# M202B.net
KiCad netlist of a schematic drawn in EAGLE
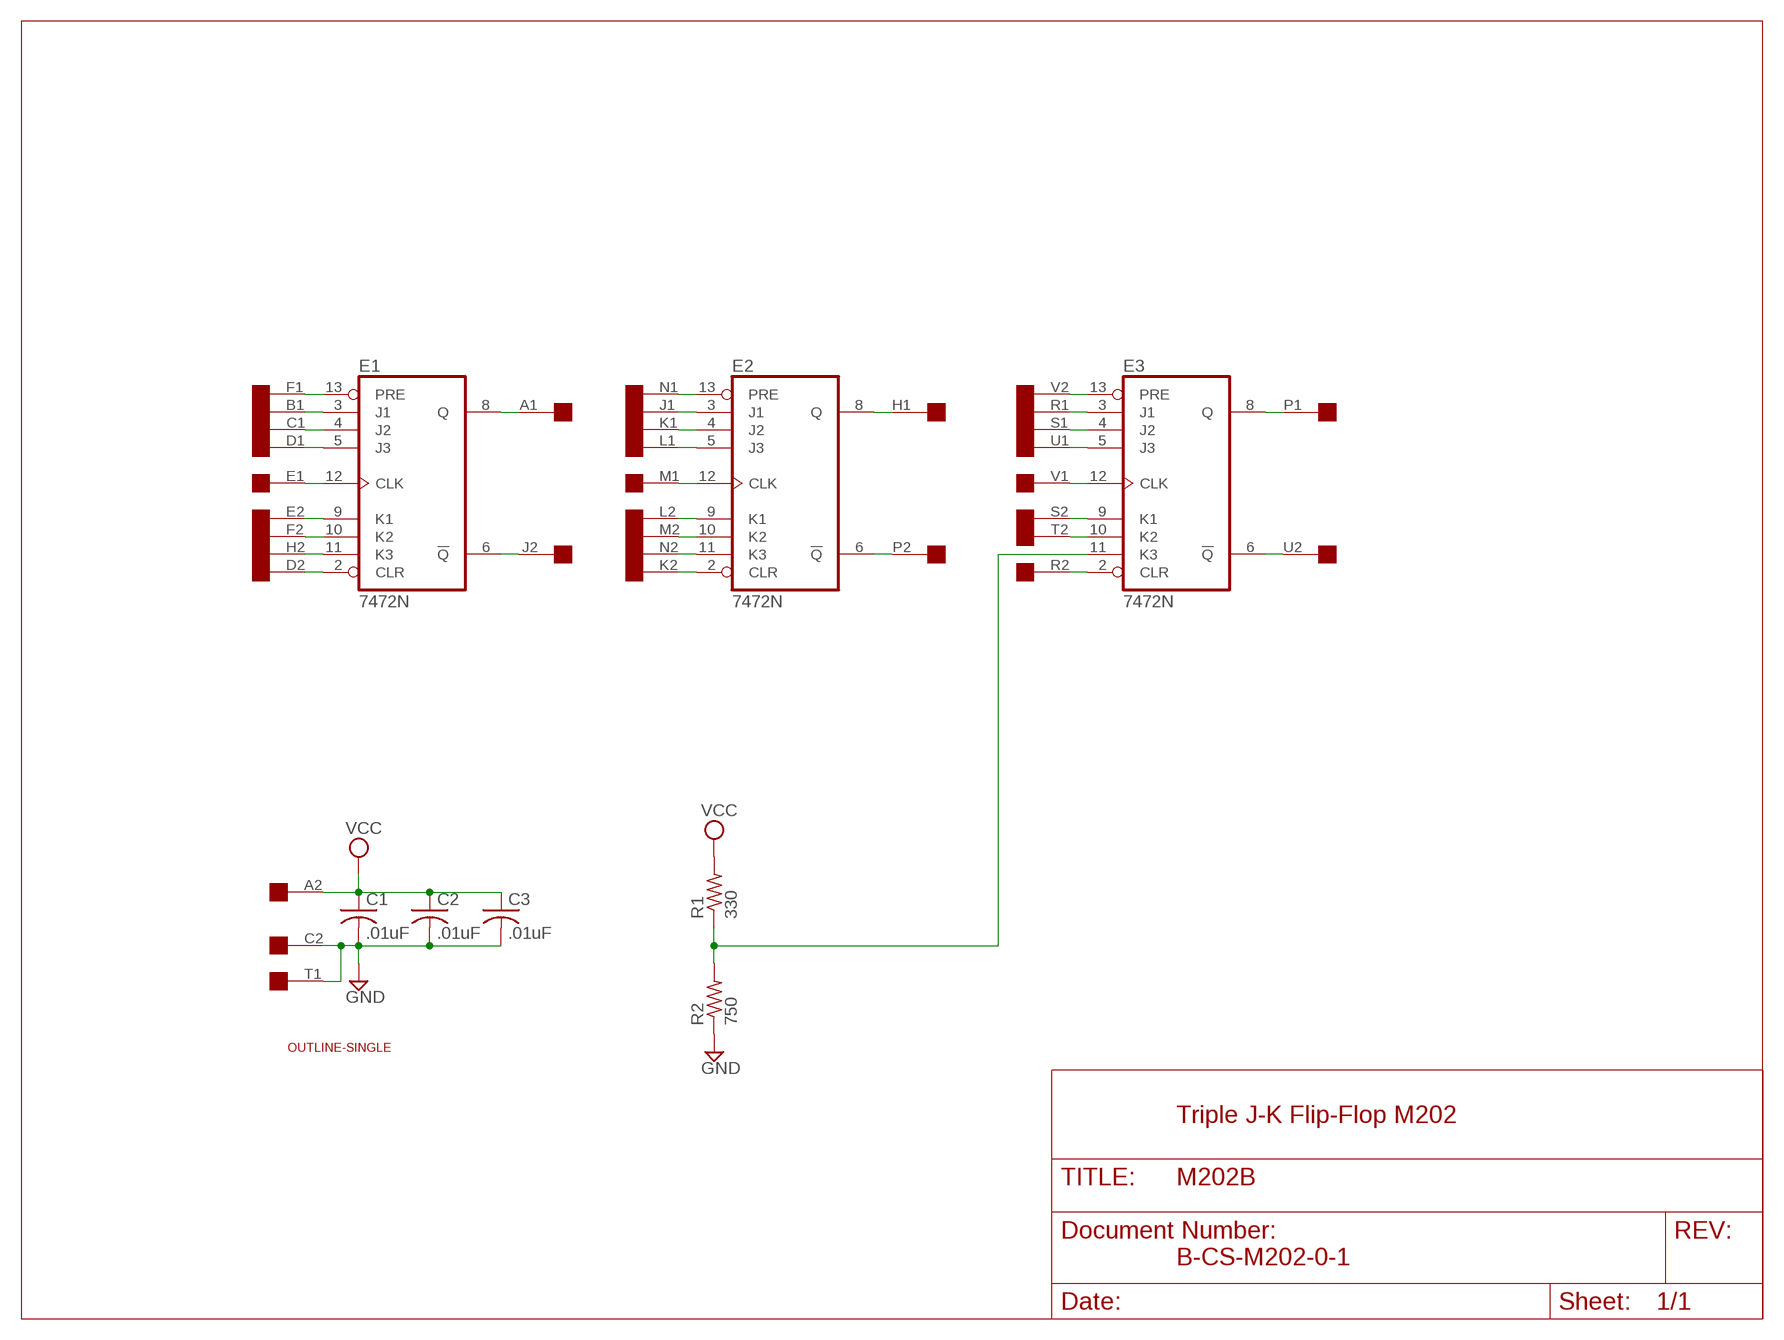
[diagram p0: schematic, sheet 1]

(export (version "E")
  (design (tool "Eeschema 10.0.6"))
  (components
    (comp (ref "C1")
      (value ".01uF")
      (footprint "eagle-import:C050-025X075")
      (libsource (lib "eagle-import") (part "C-US050-025X075"))
    )
    (comp (ref "C2")
      (value ".01uF")
      (footprint "eagle-import:C050-025X075")
      (libsource (lib "eagle-import") (part "C-US050-025X075"))
    )
    (comp (ref "C3")
      (value ".01uF")
      (footprint "eagle-import:C050-025X075")
      (libsource (lib "eagle-import") (part "C-US050-025X075"))
    )
    (comp (ref "E1")
      (value "7472N")
      (footprint "eagle-import:DIL14")
      (libsource (lib "eagle-import") (part "7472N"))
    )
    (comp (ref "E2")
      (value "7472N")
      (footprint "eagle-import:DIL14")
      (libsource (lib "eagle-import") (part "7472N"))
    )
    (comp (ref "E3")
      (value "7472N")
      (footprint "eagle-import:DIL14")
      (libsource (lib "eagle-import") (part "7472N"))
    )
    (comp (ref "R1")
      (value "330")
      (footprint "eagle-import:0207_10")
      (libsource (lib "eagle-import") (part "R-US_0207/10"))
    )
    (comp (ref "R2")
      (value "750")
      (footprint "eagle-import:0207_10")
      (libsource (lib "eagle-import") (part "R-US_0207/10"))
    )
    (comp (ref "U$1")
      (value "OUTLINE-SINGLE")
      (footprint "eagle-import:SINGLE")
      (libsource (lib "eagle-import") (part "OUTLINE-SINGLE"))
    )
    (comp (ref "U$2")
      (value "SINGLE")
      (footprint "eagle-import:EDGE-CON2")
      (libsource (lib "eagle-import") (part "SINGLE"))
    )
  )
  (nets
    (net (code "1") (name "GND") (class "Default")
      (node (ref "C1") (pin "2") (pinfunction "2_2") (pintype "passive"))
      (node (ref "C2") (pin "2") (pinfunction "2_2") (pintype "passive"))
      (node (ref "C3") (pin "2") (pinfunction "2_2") (pintype "passive"))
      (node (ref "R2") (pin "1") (pinfunction "1_1") (pintype "passive"))
      (node (ref "U$2") (pin "C2") (pinfunction "1_C2") (pintype "bidirectional"))
      (node (ref "U$2") (pin "T1") (pinfunction "1_T1") (pintype "bidirectional"))
    )
    (net (code "2") (name "Net-(E1A-CLK)") (class "Default")
      (node (ref "E1") (pin "12") (pinfunction "CLK_12") (pintype "input"))
      (node (ref "U$2") (pin "E1") (pinfunction "1_E1") (pintype "bidirectional"))
    )
    (net (code "3") (name "Net-(E1A-CLR)") (class "Default")
      (node (ref "E1") (pin "2") (pinfunction "CLR_2") (pintype "input"))
      (node (ref "U$2") (pin "D2") (pinfunction "1_D2") (pintype "bidirectional"))
    )
    (net (code "4") (name "Net-(E1A-J1)") (class "Default")
      (node (ref "E1") (pin "3") (pinfunction "J1_3") (pintype "input"))
      (node (ref "U$2") (pin "B1") (pinfunction "1_B1") (pintype "bidirectional"))
    )
    (net (code "5") (name "Net-(E1A-J2)") (class "Default")
      (node (ref "E1") (pin "4") (pinfunction "J2_4") (pintype "input"))
      (node (ref "U$2") (pin "C1") (pinfunction "1_C1") (pintype "bidirectional"))
    )
    (net (code "6") (name "Net-(E1A-J3)") (class "Default")
      (node (ref "E1") (pin "5") (pinfunction "J3_5") (pintype "input"))
      (node (ref "U$2") (pin "D1") (pinfunction "1_D1") (pintype "bidirectional"))
    )
    (net (code "7") (name "Net-(E1A-K1)") (class "Default")
      (node (ref "E1") (pin "9") (pinfunction "K1_9") (pintype "input"))
      (node (ref "U$2") (pin "E2") (pinfunction "1_E2") (pintype "bidirectional"))
    )
    (net (code "8") (name "Net-(E1A-K2)") (class "Default")
      (node (ref "E1") (pin "10") (pinfunction "K2_10") (pintype "input"))
      (node (ref "U$2") (pin "F2") (pinfunction "1_F2") (pintype "bidirectional"))
    )
    (net (code "9") (name "Net-(E1A-K3)") (class "Default")
      (node (ref "E1") (pin "11") (pinfunction "K3_11") (pintype "input"))
      (node (ref "U$2") (pin "H2") (pinfunction "1_H2") (pintype "bidirectional"))
    )
    (net (code "10") (name "Net-(E1A-PRE)") (class "Default")
      (node (ref "E1") (pin "13") (pinfunction "PRE_13") (pintype "input"))
      (node (ref "U$2") (pin "F1") (pinfunction "1_F1") (pintype "bidirectional"))
    )
    (net (code "11") (name "Net-(E1A-Q)") (class "Default")
      (node (ref "E1") (pin "8") (pinfunction "Q_8") (pintype "output"))
      (node (ref "U$2") (pin "A1") (pinfunction "1_A1") (pintype "bidirectional"))
    )
    (net (code "12") (name "Net-(E1A-~{Q})") (class "Default")
      (node (ref "E1") (pin "6") (pinfunction "~{Q}_6") (pintype "output"))
      (node (ref "U$2") (pin "J2") (pinfunction "1_J2") (pintype "bidirectional"))
    )
    (net (code "13") (name "Net-(E2A-CLK)") (class "Default")
      (node (ref "E2") (pin "12") (pinfunction "CLK_12") (pintype "input"))
      (node (ref "U$2") (pin "M1") (pinfunction "1_M1") (pintype "bidirectional"))
    )
    (net (code "14") (name "Net-(E2A-CLR)") (class "Default")
      (node (ref "E2") (pin "2") (pinfunction "CLR_2") (pintype "input"))
      (node (ref "U$2") (pin "K2") (pinfunction "1_K2") (pintype "bidirectional"))
    )
    (net (code "15") (name "Net-(E2A-J1)") (class "Default")
      (node (ref "E2") (pin "3") (pinfunction "J1_3") (pintype "input"))
      (node (ref "U$2") (pin "J1") (pinfunction "1_J1") (pintype "bidirectional"))
    )
    (net (code "16") (name "Net-(E2A-J2)") (class "Default")
      (node (ref "E2") (pin "4") (pinfunction "J2_4") (pintype "input"))
      (node (ref "U$2") (pin "K1") (pinfunction "1_K1") (pintype "bidirectional"))
    )
    (net (code "17") (name "Net-(E2A-J3)") (class "Default")
      (node (ref "E2") (pin "5") (pinfunction "J3_5") (pintype "input"))
      (node (ref "U$2") (pin "L1") (pinfunction "1_L1") (pintype "bidirectional"))
    )
    (net (code "18") (name "Net-(E2A-K1)") (class "Default")
      (node (ref "E2") (pin "9") (pinfunction "K1_9") (pintype "input"))
      (node (ref "U$2") (pin "L2") (pinfunction "1_L2") (pintype "bidirectional"))
    )
    (net (code "19") (name "Net-(E2A-K2)") (class "Default")
      (node (ref "E2") (pin "10") (pinfunction "K2_10") (pintype "input"))
      (node (ref "U$2") (pin "M2") (pinfunction "1_M2") (pintype "bidirectional"))
    )
    (net (code "20") (name "Net-(E2A-K3)") (class "Default")
      (node (ref "E2") (pin "11") (pinfunction "K3_11") (pintype "input"))
      (node (ref "U$2") (pin "N2") (pinfunction "1_N2") (pintype "bidirectional"))
    )
    (net (code "21") (name "Net-(E2A-PRE)") (class "Default")
      (node (ref "E2") (pin "13") (pinfunction "PRE_13") (pintype "input"))
      (node (ref "U$2") (pin "N1") (pinfunction "1_N1") (pintype "bidirectional"))
    )
    (net (code "22") (name "Net-(E2A-Q)") (class "Default")
      (node (ref "E2") (pin "8") (pinfunction "Q_8") (pintype "output"))
      (node (ref "U$2") (pin "H1") (pinfunction "1_H1") (pintype "bidirectional"))
    )
    (net (code "23") (name "Net-(E2A-~{Q})") (class "Default")
      (node (ref "E2") (pin "6") (pinfunction "~{Q}_6") (pintype "output"))
      (node (ref "U$2") (pin "P2") (pinfunction "1_P2") (pintype "bidirectional"))
    )
    (net (code "24") (name "Net-(E3A-CLK)") (class "Default")
      (node (ref "E3") (pin "12") (pinfunction "CLK_12") (pintype "input"))
      (node (ref "U$2") (pin "V1") (pinfunction "1_V1") (pintype "bidirectional"))
    )
    (net (code "25") (name "Net-(E3A-CLR)") (class "Default")
      (node (ref "E3") (pin "2") (pinfunction "CLR_2") (pintype "input"))
      (node (ref "U$2") (pin "R2") (pinfunction "1_R2") (pintype "bidirectional"))
    )
    (net (code "26") (name "Net-(E3A-J1)") (class "Default")
      (node (ref "E3") (pin "3") (pinfunction "J1_3") (pintype "input"))
      (node (ref "U$2") (pin "R1") (pinfunction "1_R1") (pintype "bidirectional"))
    )
    (net (code "27") (name "Net-(E3A-J2)") (class "Default")
      (node (ref "E3") (pin "4") (pinfunction "J2_4") (pintype "input"))
      (node (ref "U$2") (pin "S1") (pinfunction "1_S1") (pintype "bidirectional"))
    )
    (net (code "28") (name "Net-(E3A-J3)") (class "Default")
      (node (ref "E3") (pin "5") (pinfunction "J3_5") (pintype "input"))
      (node (ref "U$2") (pin "U1") (pinfunction "1_U1") (pintype "bidirectional"))
    )
    (net (code "29") (name "Net-(E3A-K1)") (class "Default")
      (node (ref "E3") (pin "9") (pinfunction "K1_9") (pintype "input"))
      (node (ref "U$2") (pin "S2") (pinfunction "1_S2") (pintype "bidirectional"))
    )
    (net (code "30") (name "Net-(E3A-K2)") (class "Default")
      (node (ref "E3") (pin "10") (pinfunction "K2_10") (pintype "input"))
      (node (ref "U$2") (pin "T2") (pinfunction "1_T2") (pintype "bidirectional"))
    )
    (net (code "31") (name "Net-(E3A-K3)") (class "Default")
      (node (ref "E3") (pin "11") (pinfunction "K3_11") (pintype "input"))
      (node (ref "R1") (pin "1") (pinfunction "1_1") (pintype "passive"))
      (node (ref "R2") (pin "2") (pinfunction "2_2") (pintype "passive"))
    )
    (net (code "32") (name "Net-(E3A-PRE)") (class "Default")
      (node (ref "E3") (pin "13") (pinfunction "PRE_13") (pintype "input"))
      (node (ref "U$2") (pin "V2") (pinfunction "1_V2") (pintype "bidirectional"))
    )
    (net (code "33") (name "Net-(E3A-Q)") (class "Default")
      (node (ref "E3") (pin "8") (pinfunction "Q_8") (pintype "output"))
      (node (ref "U$2") (pin "P1") (pinfunction "1_P1") (pintype "bidirectional"))
    )
    (net (code "34") (name "Net-(E3A-~{Q})") (class "Default")
      (node (ref "E3") (pin "6") (pinfunction "~{Q}_6") (pintype "output"))
      (node (ref "U$2") (pin "U2") (pinfunction "1_U2") (pintype "bidirectional"))
    )
    (net (code "35") (name "VCC") (class "Default")
      (node (ref "C1") (pin "1") (pinfunction "1_1") (pintype "passive"))
      (node (ref "C2") (pin "1") (pinfunction "1_1") (pintype "passive"))
      (node (ref "C3") (pin "1") (pinfunction "1_1") (pintype "passive"))
      (node (ref "R1") (pin "2") (pinfunction "2_2") (pintype "passive"))
      (node (ref "U$2") (pin "A2") (pinfunction "1_A2") (pintype "bidirectional"))
    )
  )
)
